# Git_test.net
KiCad netlist of a schematic drawn in EasyEDA Pro
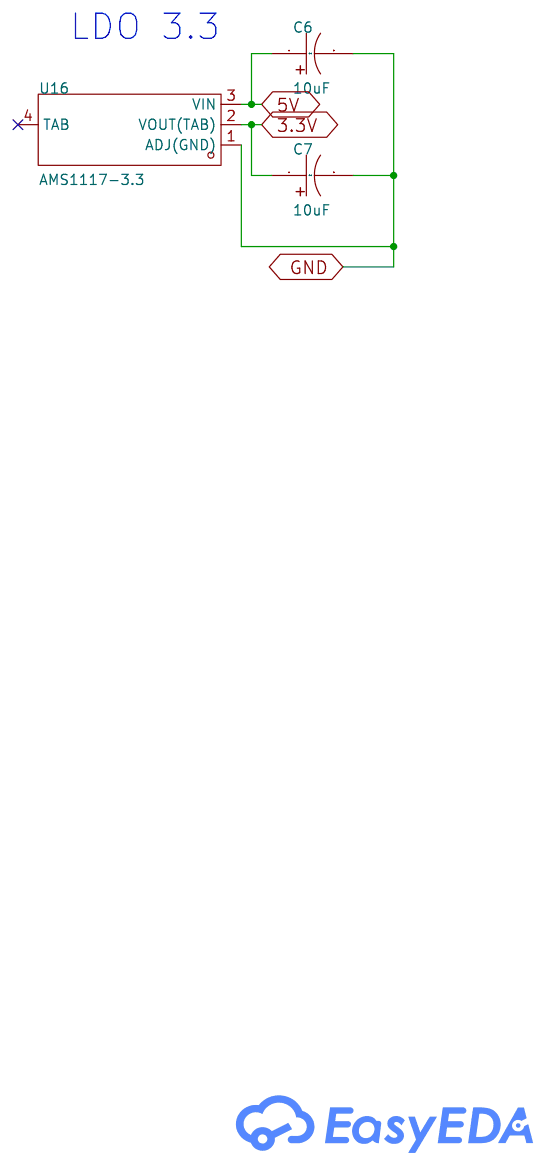
[diagram p0: schematic sheet]

(export (version "E")
  (design (tool "Eeschema 10.0.6"))
  (components
    (comp (ref "C6")
      (value "10uF")
      (footprint "easyedapro:CAP-SMD_BD4.0-L4.3-W4.3-FD-LS5.1")
      (fields (field (name "Manufacturer Part") "VSS100M1CTR-0404") (field (name "Manufacturer") "lelon(立隆)"))
      (libsource (lib "easyedapro") (part "VSS100M1C0404-TRO"))
    )
    (comp (ref "C7")
      (value "10uF")
      (footprint "easyedapro:CAP-SMD_BD4.0-L4.3-W4.3-FD-LS5.1")
      (fields (field (name "Manufacturer Part") "VSS100M1CTR-0404") (field (name "Manufacturer") "lelon(立隆)"))
      (libsource (lib "easyedapro") (part "VSS100M1C0404-TRO"))
    )
    (comp (ref "U16")
      (value "AMS1117-3.3")
      (footprint "easyedapro:SOT-223-4_L6.5-W3.5-P2.30-LS7.0-BR")
      (fields (field (name "Manufacturer") "UMW(友台半导体)"))
      (libsource (lib "easyedapro") (part "AMS1117-3.3_C347222"))
    )
  )
  (nets
    (net (code "1") (name "3.3V") (class "Default")
      (node (ref "C7") (pin "1") (pinfunction "1_1") (pintype "unspecified"))
      (node (ref "U16") (pin "2") (pinfunction "VOUT(TAB)_2") (pintype "unspecified"))
    )
    (net (code "2") (name "5V") (class "Default")
      (node (ref "C6") (pin "1") (pinfunction "1_1") (pintype "unspecified"))
      (node (ref "U16") (pin "3") (pinfunction "VIN_3") (pintype "unspecified"))
    )
    (net (code "3") (name "GND") (class "Default")
      (node (ref "C6") (pin "2") (pinfunction "2_2") (pintype "unspecified"))
      (node (ref "C7") (pin "2") (pinfunction "2_2") (pintype "unspecified"))
      (node (ref "U16") (pin "1") (pinfunction "ADJ(GND)_1") (pintype "unspecified"))
    )
    (net (code "4") (name "unconnected-(U16-TAB-Pad4)") (class "Default")
      (node (ref "U16") (pin "4") (pinfunction "TAB_4") (pintype "unspecified+no_connect"))
    )
  )
)
